# SCH_PCBBoard_2022-05-29.net
KiCad netlist of a schematic drawn in EasyEDA
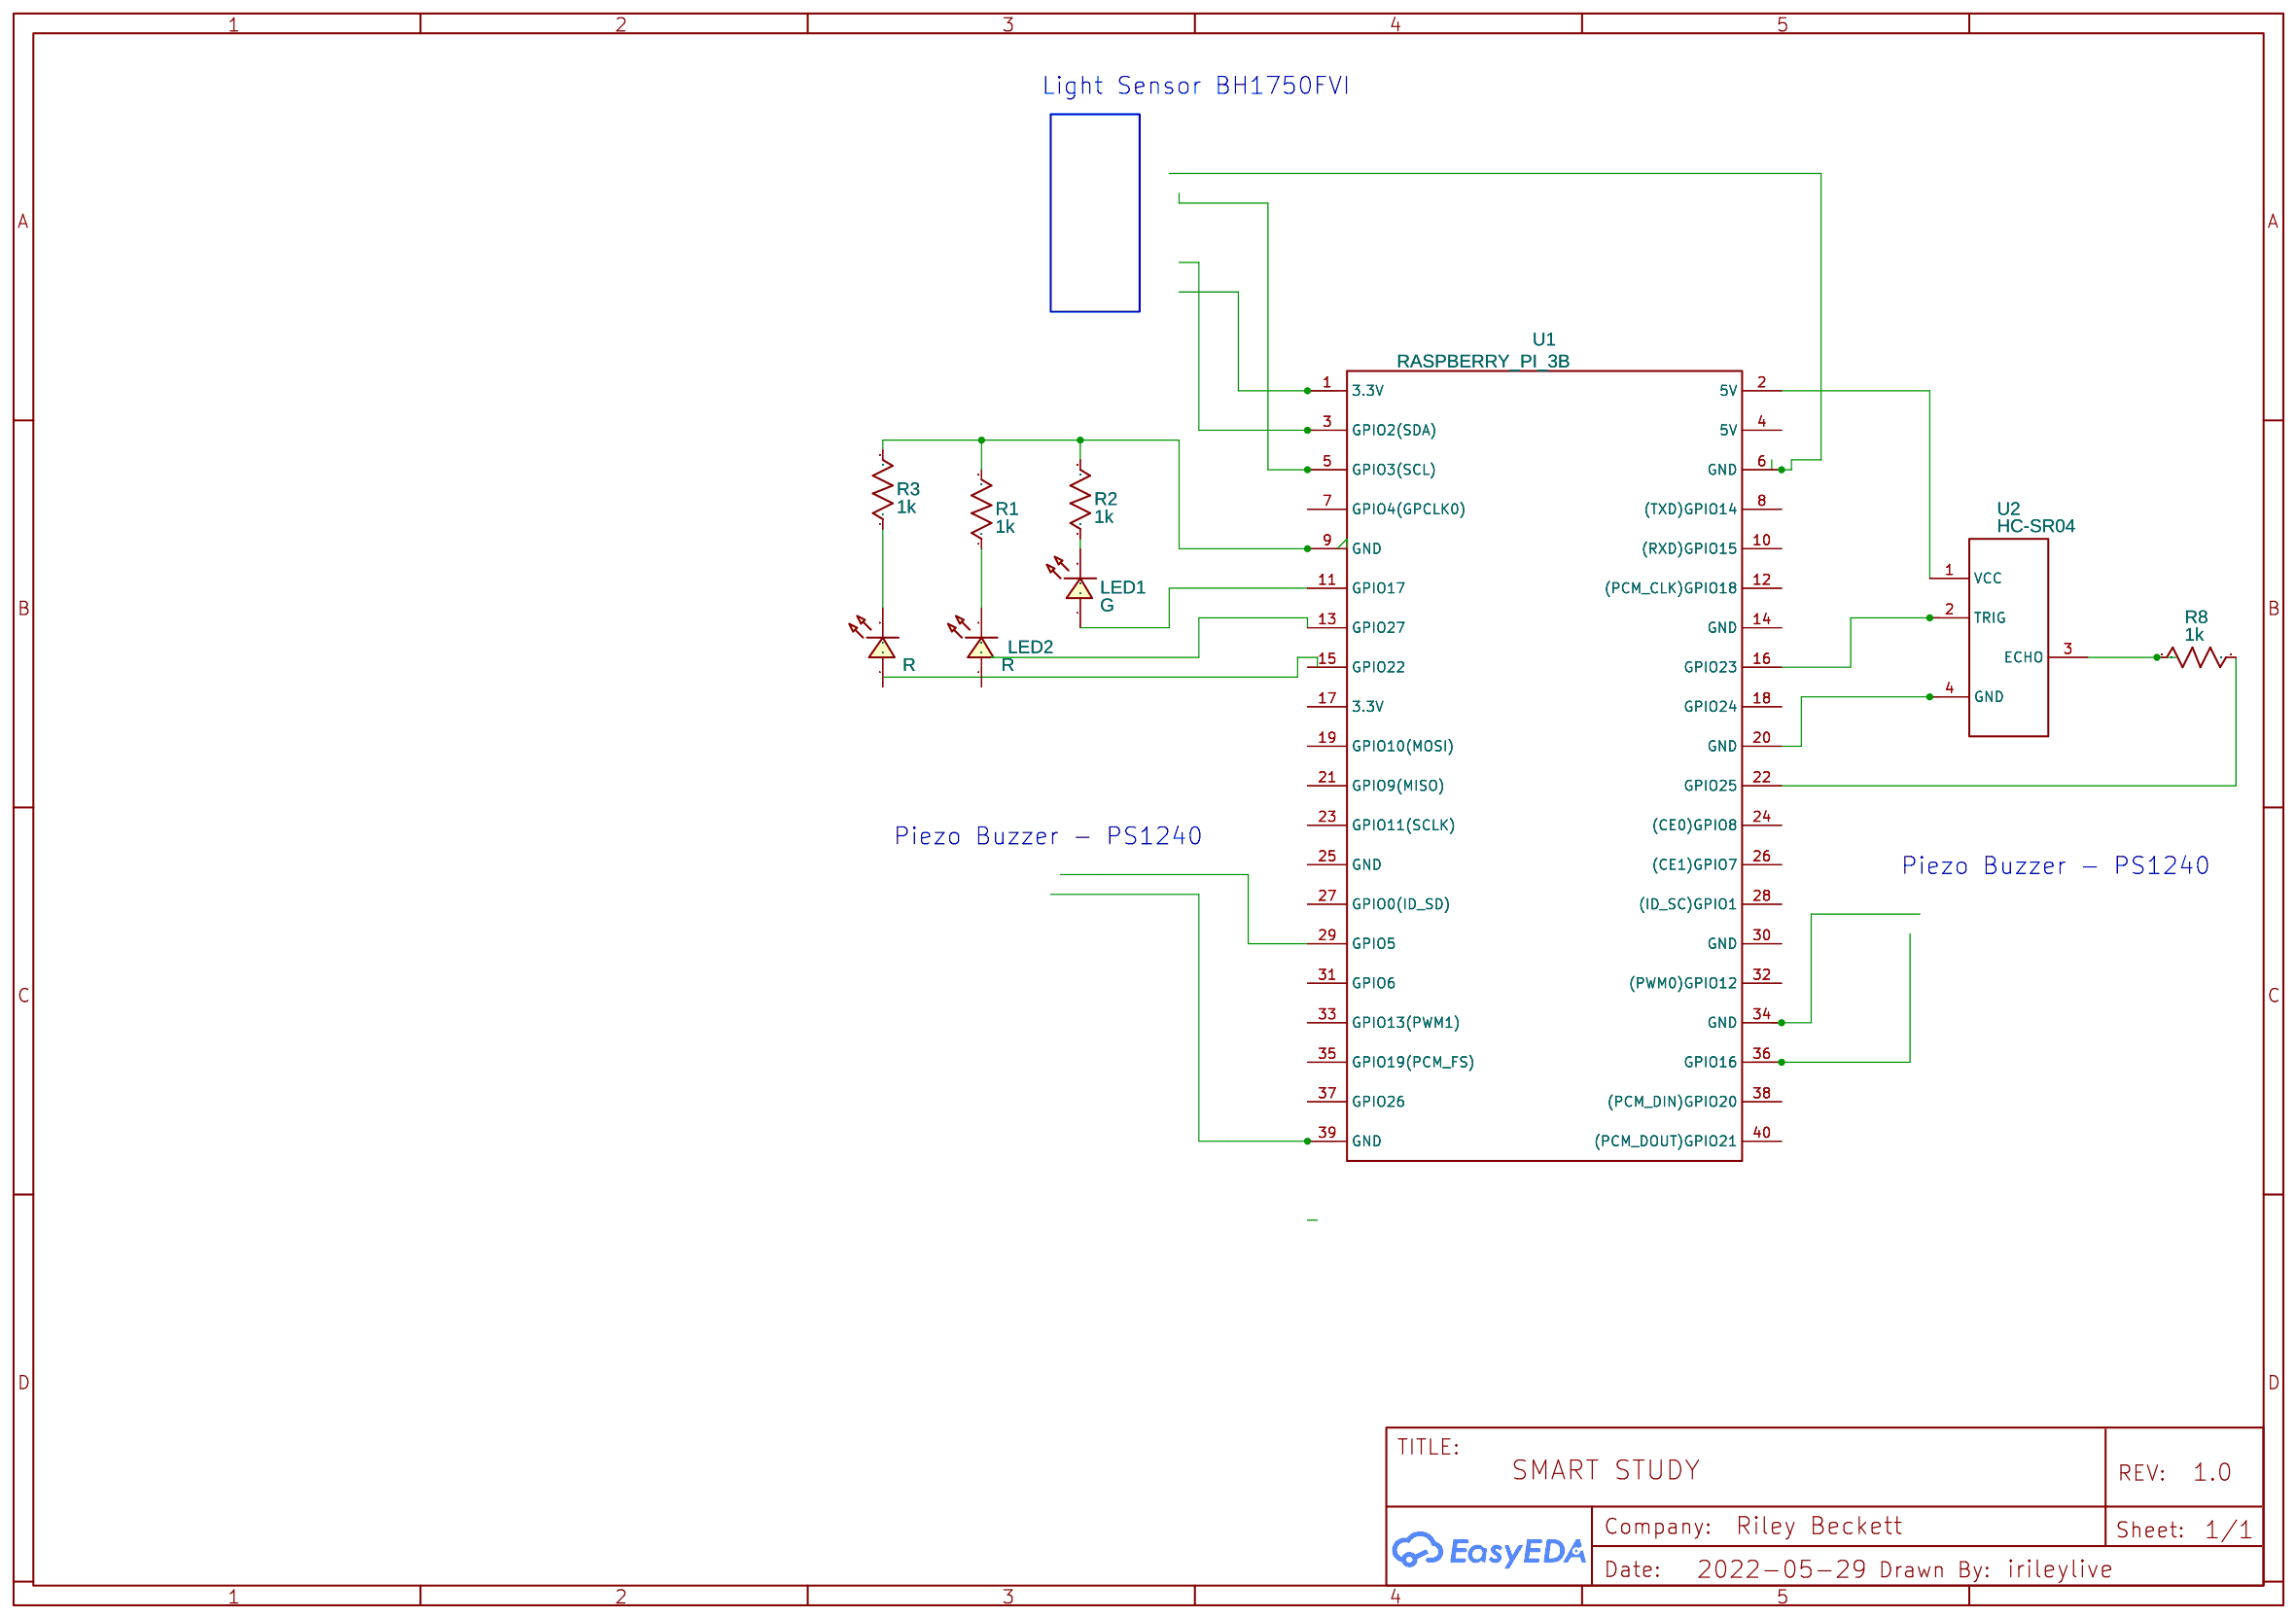
[diagram p0: schematic sheet]

(export (version "E")
  (design (tool "Eeschema 10.0.6"))
  (components
    (comp (ref "LED1")
      (value "G")
      (fields
        (field (name "BOM_Manufacturer Part") "204-10SYGD/S530-E3")
        (field (name "BOM_Supplier Part") "C85161")
      )
      (libsource (lib "") (part "LED-TH-3mm_G"))
    )
    (comp (ref "LED2")
      (value "R")
      (fields
        (field (name "BOM_Manufacturer Part") "204-10SDRD/S530-A3-L")
        (field (name "BOM_Supplier Part") "C84774")
      )
      (libsource (lib "") (part "LED-TH-3mm_R"))
    )
    (comp (ref "LED3")
      (value "R")
      (fields
        (field (name "BOM_Manufacturer Part") "204-10SDRD/S530-A3-L")
        (field (name "BOM_Supplier Part") "C84774")
      )
      (libsource (lib "") (part "LED-TH-3mm_R"))
    )
    (comp (ref "R1") (value "1k") (libsource (lib "") (part "R_AXIAL-0.3_US")))
    (comp (ref "R2") (value "1k") (libsource (lib "") (part "R_AXIAL-0.3_US")))
    (comp (ref "R3") (value "1k") (libsource (lib "") (part "R_AXIAL-0.3_US")))
    (comp (ref "R8") (value "1k") (libsource (lib "") (part "R_AXIAL-0.3_US_1")))
    (comp (ref "U1")
      (value "RASPBERRY_PI_3B")
      (fields (field (name "BOM_Manufacturer Part") "Raspberry-Pi-3B-Plus-HAT-Board"))
      (libsource (lib "") (part "RASPBERRY_PI_3B_PLUS_HAT_BOARD"))
    )
    (comp (ref "U2") (value "HC-SR04") (libsource (lib "") (part "HC-SR04")))
  )
  (nets
    (net (code "1") (name "Net-(LED1-Pad2)") (class "Default")
      (node (ref "LED1") (pin "2") (pinfunction "2_2") (pintype "unspecified"))
      (node (ref "R2") (pin "1") (pinfunction "1_1") (pintype "unspecified"))
    )
    (net (code "2") (name "Net-(LED2-Pad2)") (class "Default")
      (node (ref "LED2") (pin "2") (pinfunction "2_2") (pintype "unspecified"))
      (node (ref "R1") (pin "1") (pinfunction "1_1") (pintype "unspecified"))
    )
    (net (code "3") (name "Net-(LED3-Pad2)") (class "Default")
      (node (ref "LED3") (pin "2") (pinfunction "2_2") (pintype "unspecified"))
      (node (ref "R3") (pin "1") (pinfunction "1_1") (pintype "unspecified"))
    )
    (net (code "4") (name "Net-(R1-Pad2)") (class "Default")
      (node (ref "R1") (pin "2") (pinfunction "2_2") (pintype "unspecified"))
      (node (ref "R2") (pin "2") (pinfunction "2_2") (pintype "unspecified"))
      (node (ref "R3") (pin "2") (pinfunction "2_2") (pintype "unspecified"))
      (node (ref "U1") (pin "9") (pinfunction "GND_9") (pintype "unspecified"))
    )
    (net (code "5") (name "Net-(U1-GPIO17)") (class "Default")
      (node (ref "LED1") (pin "1") (pinfunction "1_1") (pintype "unspecified"))
      (node (ref "U1") (pin "11") (pinfunction "GPIO17_11") (pintype "unspecified"))
    )
    (net (code "6") (name "Net-(U1-GPIO23)") (class "Default")
      (node (ref "U1") (pin "16") (pinfunction "GPIO23_16") (pintype "unspecified"))
      (node (ref "U2") (pin "2") (pinfunction "TRIG_2") (pintype "unspecified"))
    )
    (net (code "7") (name "Net-(U1-GPIO25)") (class "Default")
      (node (ref "R8") (pin "1") (pinfunction "1_1") (pintype "unspecified"))
      (node (ref "U1") (pin "22") (pinfunction "GPIO25_22") (pintype "unspecified"))
    )
    (net (code "8") (name "Net-(U2-ECHO)") (class "Default")
      (node (ref "R8") (pin "2") (pinfunction "2_2") (pintype "unspecified"))
      (node (ref "U2") (pin "3") (pinfunction "ECHO_3") (pintype "unspecified"))
    )
    (net (code "9") (name "Net-(U2-GND)") (class "Default")
      (node (ref "U1") (pin "20") (pinfunction "GND_20") (pintype "unspecified"))
      (node (ref "U2") (pin "4") (pinfunction "GND_4") (pintype "unspecified"))
    )
    (net (code "10") (name "Net-(U2-VCC)") (class "Default")
      (node (ref "U1") (pin "2") (pinfunction "5V_2") (pintype "unspecified"))
      (node (ref "U2") (pin "1") (pinfunction "VCC_1") (pintype "unspecified"))
    )
    (net (code "11") (name "unconnected-(LED2-Pad1)") (class "Default")
      (node (ref "LED2") (pin "1") (pinfunction "1_1") (pintype "unspecified"))
    )
    (net (code "12") (name "unconnected-(LED3-Pad1)") (class "Default")
      (node (ref "LED3") (pin "1") (pinfunction "1_1") (pintype "unspecified"))
    )
    (net (code "13") (name "unconnected-(U1-(CE0)GPIO8-Pad24)") (class "Default")
      (node (ref "U1") (pin "24") (pinfunction "(CE0)GPIO8_24") (pintype "unspecified"))
    )
    (net (code "14") (name "unconnected-(U1-(CE1)GPIO7-Pad26)") (class "Default")
      (node (ref "U1") (pin "26") (pinfunction "(CE1)GPIO7_26") (pintype "unspecified"))
    )
    (net (code "15") (name "unconnected-(U1-(ID_SC)GPIO1-Pad28)") (class "Default")
      (node (ref "U1") (pin "28") (pinfunction "(ID_SC)GPIO1_28") (pintype "unspecified"))
    )
    (net (code "16") (name "unconnected-(U1-(PCM_CLK)GPIO18-Pad12)") (class "Default")
      (node (ref "U1") (pin "12") (pinfunction "(PCM_CLK)GPIO18_12") (pintype "unspecified"))
    )
    (net (code "17") (name "unconnected-(U1-(PCM_DIN)GPIO20-Pad38)") (class "Default")
      (node (ref "U1") (pin "38") (pinfunction "(PCM_DIN)GPIO20_38") (pintype "unspecified"))
    )
    (net (code "18") (name "unconnected-(U1-(PCM_DOUT)GPIO21-Pad40)") (class "Default")
      (node (ref "U1") (pin "40") (pinfunction "(PCM_DOUT)GPIO21_40") (pintype "unspecified"))
    )
    (net (code "19") (name "unconnected-(U1-(PWM0)GPIO12-Pad32)") (class "Default")
      (node (ref "U1") (pin "32") (pinfunction "(PWM0)GPIO12_32") (pintype "unspecified"))
    )
    (net (code "20") (name "unconnected-(U1-(RXD)GPIO15-Pad10)") (class "Default")
      (node (ref "U1") (pin "10") (pinfunction "(RXD)GPIO15_10") (pintype "unspecified"))
    )
    (net (code "21") (name "unconnected-(U1-(TXD)GPIO14-Pad8)") (class "Default")
      (node (ref "U1") (pin "8") (pinfunction "(TXD)GPIO14_8") (pintype "unspecified"))
    )
    (net (code "22") (name "unconnected-(U1-3.3V-Pad1)") (class "Default")
      (node (ref "U1") (pin "1") (pinfunction "3.3V_1") (pintype "unspecified"))
    )
    (net (code "23") (name "unconnected-(U1-3.3V-Pad17)") (class "Default")
      (node (ref "U1") (pin "17") (pinfunction "3.3V_17") (pintype "unspecified"))
    )
    (net (code "24") (name "unconnected-(U1-5V-Pad4)") (class "Default")
      (node (ref "U1") (pin "4") (pinfunction "5V_4") (pintype "unspecified"))
    )
    (net (code "25") (name "unconnected-(U1-GND-Pad6)") (class "Default")
      (node (ref "U1") (pin "6") (pinfunction "GND_6") (pintype "unspecified"))
    )
    (net (code "26") (name "unconnected-(U1-GND-Pad14)") (class "Default")
      (node (ref "U1") (pin "14") (pinfunction "GND_14") (pintype "unspecified"))
    )
    (net (code "27") (name "unconnected-(U1-GND-Pad25)") (class "Default")
      (node (ref "U1") (pin "25") (pinfunction "GND_25") (pintype "unspecified"))
    )
    (net (code "28") (name "unconnected-(U1-GND-Pad30)") (class "Default")
      (node (ref "U1") (pin "30") (pinfunction "GND_30") (pintype "unspecified"))
    )
    (net (code "29") (name "unconnected-(U1-GND-Pad34)") (class "Default")
      (node (ref "U1") (pin "34") (pinfunction "GND_34") (pintype "unspecified"))
    )
    (net (code "30") (name "unconnected-(U1-GND-Pad39)") (class "Default")
      (node (ref "U1") (pin "39") (pinfunction "GND_39") (pintype "unspecified"))
    )
    (net (code "31") (name "unconnected-(U1-GPIO0(ID_SD)-Pad27)") (class "Default")
      (node (ref "U1") (pin "27") (pinfunction "GPIO0(ID_SD)_27") (pintype "unspecified"))
    )
    (net (code "32") (name "unconnected-(U1-GPIO2(SDA)-Pad3)") (class "Default")
      (node (ref "U1") (pin "3") (pinfunction "GPIO2(SDA)_3") (pintype "unspecified"))
    )
    (net (code "33") (name "unconnected-(U1-GPIO3(SCL)-Pad5)") (class "Default")
      (node (ref "U1") (pin "5") (pinfunction "GPIO3(SCL)_5") (pintype "unspecified"))
    )
    (net (code "34") (name "unconnected-(U1-GPIO4(GPCLK0)-Pad7)") (class "Default")
      (node (ref "U1") (pin "7") (pinfunction "GPIO4(GPCLK0)_7") (pintype "unspecified"))
    )
    (net (code "35") (name "unconnected-(U1-GPIO5-Pad29)") (class "Default")
      (node (ref "U1") (pin "29") (pinfunction "GPIO5_29") (pintype "unspecified"))
    )
    (net (code "36") (name "unconnected-(U1-GPIO6-Pad31)") (class "Default")
      (node (ref "U1") (pin "31") (pinfunction "GPIO6_31") (pintype "unspecified"))
    )
    (net (code "37") (name "unconnected-(U1-GPIO9(MISO)-Pad21)") (class "Default")
      (node (ref "U1") (pin "21") (pinfunction "GPIO9(MISO)_21") (pintype "unspecified"))
    )
    (net (code "38") (name "unconnected-(U1-GPIO10(MOSI)-Pad19)") (class "Default")
      (node (ref "U1") (pin "19") (pinfunction "GPIO10(MOSI)_19") (pintype "unspecified"))
    )
    (net (code "39") (name "unconnected-(U1-GPIO11(SCLK)-Pad23)") (class "Default")
      (node (ref "U1") (pin "23") (pinfunction "GPIO11(SCLK)_23") (pintype "unspecified"))
    )
    (net (code "40") (name "unconnected-(U1-GPIO13(PWM1)-Pad33)") (class "Default")
      (node (ref "U1") (pin "33") (pinfunction "GPIO13(PWM1)_33") (pintype "unspecified"))
    )
    (net (code "41") (name "unconnected-(U1-GPIO16-Pad36)") (class "Default")
      (node (ref "U1") (pin "36") (pinfunction "GPIO16_36") (pintype "unspecified"))
    )
    (net (code "42") (name "unconnected-(U1-GPIO19(PCM_FS)-Pad35)") (class "Default")
      (node (ref "U1") (pin "35") (pinfunction "GPIO19(PCM_FS)_35") (pintype "unspecified"))
    )
    (net (code "43") (name "unconnected-(U1-GPIO22-Pad15)") (class "Default")
      (node (ref "U1") (pin "15") (pinfunction "GPIO22_15") (pintype "unspecified"))
    )
    (net (code "44") (name "unconnected-(U1-GPIO24-Pad18)") (class "Default")
      (node (ref "U1") (pin "18") (pinfunction "GPIO24_18") (pintype "unspecified"))
    )
    (net (code "45") (name "unconnected-(U1-GPIO26-Pad37)") (class "Default")
      (node (ref "U1") (pin "37") (pinfunction "GPIO26_37") (pintype "unspecified"))
    )
    (net (code "46") (name "unconnected-(U1-GPIO27-Pad13)") (class "Default")
      (node (ref "U1") (pin "13") (pinfunction "GPIO27_13") (pintype "unspecified"))
    )
  )
)
